# Schematic.net
KiCad netlist of a schematic drawn in Altium Designer
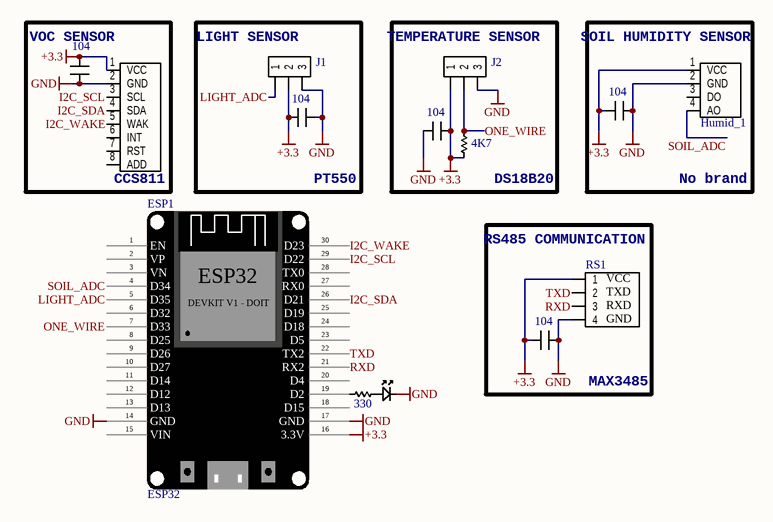
[diagram p0: Schematic.SchDoc]

(export (version "E")
  (design (tool "Eeschema 10.0.6"))
  (components
    (comp (ref "C1")
      (value "104")
      (footprint "CAP-CERAMIC-100mil")
      (description "Capacitor")
      (libsource (lib "Minh-An DAO") (part "CAP"))
    )
    (comp (ref "C2")
      (value "104")
      (footprint "CAP-CERAMIC-100mil")
      (description "Capacitor")
      (libsource (lib "Minh-An DAO") (part "CAP"))
    )
    (comp (ref "C3")
      (value "104")
      (footprint "CAP-CERAMIC-100mil")
      (description "Capacitor")
      (libsource (lib "Minh-An DAO") (part "CAP"))
    )
    (comp (ref "C4")
      (value "104")
      (footprint "CAP-CERAMIC-100mil")
      (description "Capacitor")
      (libsource (lib "Minh-An DAO") (part "CAP"))
    )
    (comp (ref "C5")
      (value "104")
      (footprint "CAP-CERAMIC-100mil")
      (description "Capacitor")
      (libsource (lib "Minh-An DAO") (part "CAP"))
    )
    (comp (ref "CCS1")
      (value "CCS811_HDC1080")
      (footprint "CSS811-MODULE-TER-J8x1-F-2.54mm")
      (description "https://www.thegioiic.com/products/ccs811-mach-cam-bien-khi-co-chat-luong-khong-khi")
      (libsource (lib "Sch") (part "CCS811_HDC1080"))
    )
    (comp (ref "ESP1")
      (value "ESP32")
      (footprint "2#ESP32_DEVKIT_V1")
      (libsource (lib "Sch") (part "2#B#ESP32_DOIT_DEVKIT_V1"))
    )
    (comp (ref "Humid_1")
      (value "Soil Humidity Sensor")
      (footprint "SOIL_HUMID_TER-J4x1-F-2.54mm")
      (description "https://www.thegioiic.com/products/cam-bien-do-am-dat-dau-do-chong-an-mon")
      (libsource (lib "Sch") (part "Soil Humidity Sensor"))
    )
    (comp (ref "J1")
      (value "Header")
      (footprint "TER-J3x1-M-2.54mm")
      (libsource (lib "Minh-An DAO") (part "Header 3x1"))
    )
    (comp (ref "J2")
      (value "Header")
      (footprint "TER-J3x1-M-2.54mm")
      (libsource (lib "Minh-An DAO") (part "Header 3x1"))
    )
    (comp (ref "LED1")
      (value "LED")
      (footprint "TER-H2")
      (description "Light Emitting Diode")
      (fields (field (name "PUBLISHER") "Altium Limited"))
      (libsource (lib "Minh-An DAO") (part "LED"))
    )
    (comp (ref "R1")
      (value "4K7")
      (footprint "RES-HOLE-1/8W")
      (description "Resistor")
      (libsource (lib "Minh-An DAO") (part "RES"))
    )
    (comp (ref "R2")
      (value "330")
      (footprint "RES-HOLE-1/8W")
      (description "Resistor")
      (libsource (lib "Minh-An DAO") (part "RES"))
    )
    (comp (ref "RS1")
      (value "RS485-Module")
      (footprint "5#RS485 to TTL - SIMPLIFIED")
      (description "https://www.thegioiic.com/products/mach-chuyen-doi-rs485-to-ttl")
      (libsource (lib "Sch") (part "5#RS485 to TTL - simplified"))
    )
  )
  (nets
    (net (code "1") (name "+3.3") (class "Default")
      (node (ref "C1") (pin "2") (pinfunction "2_2") (pintype "passive"))
      (node (ref "C2") (pin "1") (pinfunction "1_1") (pintype "passive"))
      (node (ref "C3") (pin "1") (pinfunction "1_1") (pintype "passive"))
      (node (ref "C4") (pin "2") (pinfunction "2_2") (pintype "passive"))
      (node (ref "C5") (pin "1") (pinfunction "1_1") (pintype "passive"))
      (node (ref "CCS1") (pin "1") (pinfunction "VCC_1") (pintype "passive"))
      (node (ref "ESP1") (pin "16") (pinfunction "3.3V_16") (pintype "passive"))
      (node (ref "Humid_1") (pin "1") (pinfunction "VCC_1") (pintype "passive"))
      (node (ref "J1") (pin "2") (pinfunction "2_2") (pintype "passive"))
      (node (ref "J2") (pin "1") (pinfunction "1_1") (pintype "passive"))
      (node (ref "R1") (pin "1") (pinfunction "1_1") (pintype "passive"))
      (node (ref "RS1") (pin "1") (pinfunction "1_1") (pintype "passive"))
    )
    (net (code "2") (name "/I2C_SCL") (class "Default")
      (node (ref "CCS1") (pin "3") (pinfunction "SCL_3") (pintype "passive"))
      (node (ref "ESP1") (pin "29") (pinfunction "D22_29") (pintype "passive"))
    )
    (net (code "3") (name "/I2C_SDA") (class "Default")
      (node (ref "CCS1") (pin "4") (pinfunction "SDA_4") (pintype "passive"))
      (node (ref "ESP1") (pin "26") (pinfunction "D21_26") (pintype "passive"))
    )
    (net (code "4") (name "/I2C_WAKE") (class "Default")
      (node (ref "CCS1") (pin "5") (pinfunction "WAK_5") (pintype "passive"))
      (node (ref "ESP1") (pin "30") (pinfunction "D23_30") (pintype "passive"))
    )
    (net (code "5") (name "/LIGHT_ADC") (class "Default")
      (node (ref "ESP1") (pin "5") (pinfunction "D35_5") (pintype "passive"))
      (node (ref "J1") (pin "1") (pinfunction "1_1") (pintype "passive"))
    )
    (net (code "6") (name "/ONE_WIRE") (class "Default")
      (node (ref "ESP1") (pin "7") (pinfunction "D33_7") (pintype "passive"))
      (node (ref "J2") (pin "2") (pinfunction "2_2") (pintype "passive"))
      (node (ref "R1") (pin "2") (pinfunction "2_2") (pintype "passive"))
    )
    (net (code "7") (name "/RXD") (class "Default")
      (node (ref "ESP1") (pin "21") (pinfunction "RX2_21") (pintype "passive"))
      (node (ref "RS1") (pin "3") (pinfunction "3_3") (pintype "passive"))
    )
    (net (code "8") (name "/SOIL_ADC") (class "Default")
      (node (ref "ESP1") (pin "4") (pinfunction "D34_4") (pintype "passive"))
      (node (ref "Humid_1") (pin "4") (pinfunction "AO_4") (pintype "passive"))
    )
    (net (code "9") (name "/TXD") (class "Default")
      (node (ref "ESP1") (pin "22") (pinfunction "TX2_22") (pintype "passive"))
      (node (ref "RS1") (pin "2") (pinfunction "2_2") (pintype "passive"))
    )
    (net (code "10") (name "GND") (class "Default")
      (node (ref "C1") (pin "1") (pinfunction "1_1") (pintype "passive"))
      (node (ref "C2") (pin "2") (pinfunction "2_2") (pintype "passive"))
      (node (ref "C3") (pin "2") (pinfunction "2_2") (pintype "passive"))
      (node (ref "C4") (pin "1") (pinfunction "1_1") (pintype "passive"))
      (node (ref "C5") (pin "2") (pinfunction "2_2") (pintype "passive"))
      (node (ref "CCS1") (pin "2") (pinfunction "GND_2") (pintype "passive"))
      (node (ref "ESP1") (pin "14") (pinfunction "GND_14") (pintype "passive"))
      (node (ref "ESP1") (pin "17") (pinfunction "GND_17") (pintype "passive"))
      (node (ref "Humid_1") (pin "2") (pinfunction "GND_2") (pintype "passive"))
      (node (ref "J1") (pin "3") (pinfunction "3_3") (pintype "passive"))
      (node (ref "J2") (pin "3") (pinfunction "3_3") (pintype "passive"))
      (node (ref "LED1") (pin "2") (pinfunction "K_2") (pintype "passive"))
      (node (ref "RS1") (pin "4") (pinfunction "4_4") (pintype "passive"))
    )
    (net (code "11") (name "Net-(ESP1-D2)") (class "Default")
      (node (ref "ESP1") (pin "19") (pinfunction "D2_19") (pintype "passive"))
      (node (ref "R2") (pin "2") (pinfunction "2_2") (pintype "passive"))
    )
    (net (code "12") (name "Net-(LED1-A)") (class "Default")
      (node (ref "LED1") (pin "1") (pinfunction "A_1") (pintype "passive"))
      (node (ref "R2") (pin "1") (pinfunction "1_1") (pintype "passive"))
    )
    (net (code "13") (name "unconnected-(CCS1-ADD-Pad8)") (class "Default")
      (node (ref "CCS1") (pin "8") (pinfunction "ADD_8") (pintype "passive"))
    )
    (net (code "14") (name "unconnected-(CCS1-INT-Pad6)") (class "Default")
      (node (ref "CCS1") (pin "6") (pinfunction "INT_6") (pintype "passive"))
    )
    (net (code "15") (name "unconnected-(CCS1-RST-Pad7)") (class "Default")
      (node (ref "CCS1") (pin "7") (pinfunction "RST_7") (pintype "passive"))
    )
    (net (code "16") (name "unconnected-(ESP1-D4-Pad20)") (class "Default")
      (node (ref "ESP1") (pin "20") (pinfunction "D4_20") (pintype "passive"))
    )
    (net (code "17") (name "unconnected-(ESP1-D5-Pad23)") (class "Default")
      (node (ref "ESP1") (pin "23") (pinfunction "D5_23") (pintype "passive"))
    )
    (net (code "18") (name "unconnected-(ESP1-D12-Pad12)") (class "Default")
      (node (ref "ESP1") (pin "12") (pinfunction "D12_12") (pintype "passive"))
    )
    (net (code "19") (name "unconnected-(ESP1-D13-Pad13)") (class "Default")
      (node (ref "ESP1") (pin "13") (pinfunction "D13_13") (pintype "passive"))
    )
    (net (code "20") (name "unconnected-(ESP1-D14-Pad11)") (class "Default")
      (node (ref "ESP1") (pin "11") (pinfunction "D14_11") (pintype "passive"))
    )
    (net (code "21") (name "unconnected-(ESP1-D15-Pad18)") (class "Default")
      (node (ref "ESP1") (pin "18") (pinfunction "D15_18") (pintype "passive"))
    )
    (net (code "22") (name "unconnected-(ESP1-D18-Pad24)") (class "Default")
      (node (ref "ESP1") (pin "24") (pinfunction "D18_24") (pintype "passive"))
    )
    (net (code "23") (name "unconnected-(ESP1-D19-Pad25)") (class "Default")
      (node (ref "ESP1") (pin "25") (pinfunction "D19_25") (pintype "passive"))
    )
    (net (code "24") (name "unconnected-(ESP1-D25-Pad8)") (class "Default")
      (node (ref "ESP1") (pin "8") (pinfunction "D25_8") (pintype "passive"))
    )
    (net (code "25") (name "unconnected-(ESP1-D26-Pad9)") (class "Default")
      (node (ref "ESP1") (pin "9") (pinfunction "D26_9") (pintype "passive"))
    )
    (net (code "26") (name "unconnected-(ESP1-D27-Pad10)") (class "Default")
      (node (ref "ESP1") (pin "10") (pinfunction "D27_10") (pintype "passive"))
    )
    (net (code "27") (name "unconnected-(ESP1-D32-Pad6)") (class "Default")
      (node (ref "ESP1") (pin "6") (pinfunction "D32_6") (pintype "passive"))
    )
    (net (code "28") (name "unconnected-(ESP1-EN-Pad1)") (class "Default")
      (node (ref "ESP1") (pin "1") (pinfunction "EN_1") (pintype "passive"))
    )
    (net (code "29") (name "unconnected-(ESP1-RX0-Pad27)") (class "Default")
      (node (ref "ESP1") (pin "27") (pinfunction "RX0_27") (pintype "passive"))
    )
    (net (code "30") (name "unconnected-(ESP1-TX0-Pad28)") (class "Default")
      (node (ref "ESP1") (pin "28") (pinfunction "TX0_28") (pintype "passive"))
    )
    (net (code "31") (name "unconnected-(ESP1-VIN-Pad15)") (class "Default")
      (node (ref "ESP1") (pin "15") (pinfunction "VIN_15") (pintype "passive"))
    )
    (net (code "32") (name "unconnected-(ESP1-VN-Pad3)") (class "Default")
      (node (ref "ESP1") (pin "3") (pinfunction "VN_3") (pintype "passive"))
    )
    (net (code "33") (name "unconnected-(ESP1-VP-Pad2)") (class "Default")
      (node (ref "ESP1") (pin "2") (pinfunction "VP_2") (pintype "passive"))
    )
    (net (code "34") (name "unconnected-(Humid_1-DO-Pad3)") (class "Default")
      (node (ref "Humid_1") (pin "3") (pinfunction "DO_3") (pintype "passive"))
    )
  )
)
